# 0123-class-d-amp-max98365.net
KiCad netlist of a schematic drawn in EAGLE
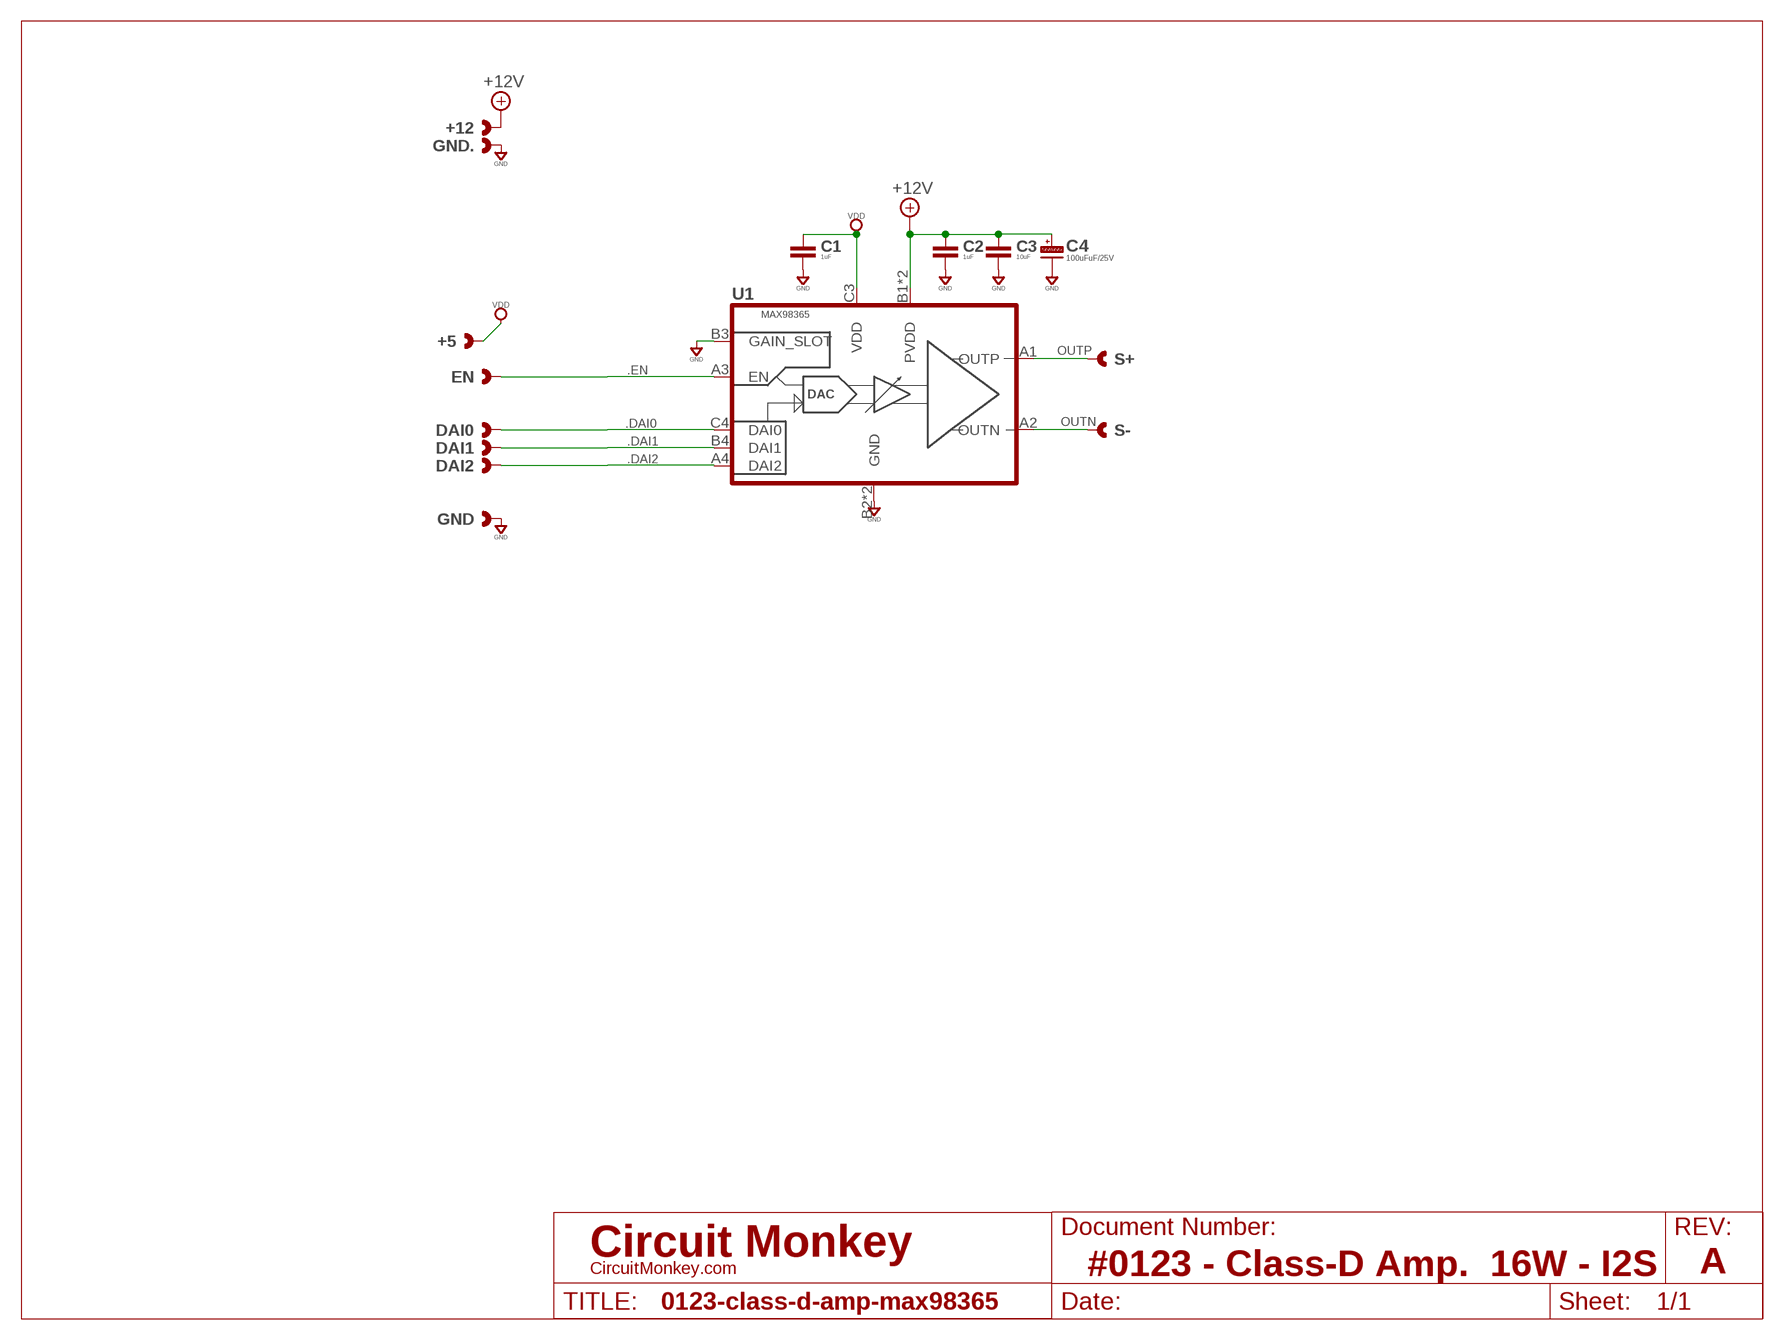
[diagram p0: schematic, sheet 1]

(export (version "E")
  (design (tool "Eeschema 10.0.6"))
  (components
    (comp (ref "+5")
      (value "CAST-01X12.00MM")
      (footprint "eagle-import:CAST01-2.00MM")
      (libsource (lib "eagle-import") (part "CAST-01X12.00MM"))
    )
    (comp (ref "+12")
      (value "CAST-01X12.00MM")
      (footprint "eagle-import:CAST01-2.00MM")
      (libsource (lib "eagle-import") (part "CAST-01X12.00MM"))
    )
    (comp (ref "C1")
      (value "1uF")
      (footprint "eagle-import:0603-CAP")
      (libsource (lib "eagle-import") (part "CAPACITOR0603"))
    )
    (comp (ref "C2")
      (value "1uF")
      (footprint "eagle-import:0603-CAP")
      (libsource (lib "eagle-import") (part "CAPACITOR0603"))
    )
    (comp (ref "C3")
      (value "10uF")
      (footprint "eagle-import:0603-CAP")
      (libsource (lib "eagle-import") (part "CAPACITOR0603"))
    )
    (comp (ref "C4")
      (value "100uFuF/25V")
      (footprint "eagle-import:CAP_ALUM_SMT_6.3")
      (libsource (lib "eagle-import") (part "CAPACITOR_POL-ALUM-SMT-6.3"))
    )
    (comp (ref "DAI0")
      (value "CAST-01X12.00MM")
      (footprint "eagle-import:CAST01-2.00MM")
      (libsource (lib "eagle-import") (part "CAST-01X12.00MM"))
    )
    (comp (ref "DAI1")
      (value "CAST-01X12.00MM")
      (footprint "eagle-import:CAST01-2.00MM")
      (libsource (lib "eagle-import") (part "CAST-01X12.00MM"))
    )
    (comp (ref "DAI2")
      (value "CAST-01X12.00MM")
      (footprint "eagle-import:CAST01-2.00MM")
      (libsource (lib "eagle-import") (part "CAST-01X12.00MM"))
    )
    (comp (ref "EN")
      (value "CAST-01X12.00MM")
      (footprint "eagle-import:CAST01-2.00MM")
      (libsource (lib "eagle-import") (part "CAST-01X12.00MM"))
    )
    (comp (ref "GND")
      (value "CAST-01X12.00MM")
      (footprint "eagle-import:CAST01-2.00MM")
      (libsource (lib "eagle-import") (part "CAST-01X12.00MM"))
    )
    (comp (ref "GND.")
      (value "CAST-01X12.00MM")
      (footprint "eagle-import:CAST01-2.00MM")
      (libsource (lib "eagle-import") (part "CAST-01X12.00MM"))
    )
    (comp (ref "S+")
      (value "CAST-01X12.00MM")
      (footprint "eagle-import:CAST01-2.00MM")
      (libsource (lib "eagle-import") (part "CAST-01X12.00MM"))
    )
    (comp (ref "S-")
      (value "CAST-01X12.00MM")
      (footprint "eagle-import:CAST01-2.00MM")
      (libsource (lib "eagle-import") (part "CAST-01X12.00MM"))
    )
    (comp (ref "U1")
      (value "MAX98365")
      (footprint "eagle-import:12WLP")
      (fields (field (name "MFR") "Maxim") (field (name "MPN") "MAX98365A/C"))
      (libsource (lib "eagle-import") (part "MAX98365"))
    )
  )
  (nets
    (net (code "1") (name "+12V") (class "Default")
      (node (ref "+12") (pin "1") (pinfunction "1_1") (pintype "bidirectional"))
      (node (ref "+12") (pin "P$1") (pinfunction "1_P$1") (pintype "bidirectional"))
      (node (ref "+12") (pin "P$2") (pinfunction "1_P$2") (pintype "bidirectional"))
      (node (ref "C2") (pin "1") (pinfunction "1_1") (pintype "passive"))
      (node (ref "C3") (pin "1") (pinfunction "1_1") (pintype "passive"))
      (node (ref "C4") (pin "+") (pinfunction "P_+") (pintype "bidirectional"))
      (node (ref "U1") (pin "B1") (pinfunction "PVDD_B1") (pintype "bidirectional"))
      (node (ref "U1") (pin "C1") (pinfunction "PVDD_C1") (pintype "bidirectional"))
    )
    (net (code "2") (name "/.DAI0") (class "Default")
      (node (ref "DAI0") (pin "1") (pinfunction "1_1") (pintype "bidirectional"))
      (node (ref "DAI0") (pin "P$1") (pinfunction "1_P$1") (pintype "bidirectional"))
      (node (ref "DAI0") (pin "P$2") (pinfunction "1_P$2") (pintype "bidirectional"))
      (node (ref "U1") (pin "C4") (pinfunction "DAI0_C4") (pintype "bidirectional"))
    )
    (net (code "3") (name "/.DAI1") (class "Default")
      (node (ref "DAI1") (pin "1") (pinfunction "1_1") (pintype "bidirectional"))
      (node (ref "DAI1") (pin "P$1") (pinfunction "1_P$1") (pintype "bidirectional"))
      (node (ref "DAI1") (pin "P$2") (pinfunction "1_P$2") (pintype "bidirectional"))
      (node (ref "U1") (pin "B4") (pinfunction "DAI1_B4") (pintype "bidirectional"))
    )
    (net (code "4") (name "/.DAI2") (class "Default")
      (node (ref "DAI2") (pin "1") (pinfunction "1_1") (pintype "bidirectional"))
      (node (ref "DAI2") (pin "P$1") (pinfunction "1_P$1") (pintype "bidirectional"))
      (node (ref "DAI2") (pin "P$2") (pinfunction "1_P$2") (pintype "bidirectional"))
      (node (ref "U1") (pin "A4") (pinfunction "DAI2_A4") (pintype "bidirectional"))
    )
    (net (code "5") (name "/.EN") (class "Default")
      (node (ref "EN") (pin "1") (pinfunction "1_1") (pintype "bidirectional"))
      (node (ref "EN") (pin "P$1") (pinfunction "1_P$1") (pintype "bidirectional"))
      (node (ref "EN") (pin "P$2") (pinfunction "1_P$2") (pintype "bidirectional"))
      (node (ref "U1") (pin "A3") (pinfunction "EN_A3") (pintype "bidirectional"))
    )
    (net (code "6") (name "/OUTN") (class "Default")
      (node (ref "S-") (pin "1") (pinfunction "1_1") (pintype "bidirectional"))
      (node (ref "S-") (pin "P$1") (pinfunction "1_P$1") (pintype "bidirectional"))
      (node (ref "S-") (pin "P$2") (pinfunction "1_P$2") (pintype "bidirectional"))
      (node (ref "U1") (pin "A2") (pinfunction "OUTN_A2") (pintype "bidirectional"))
    )
    (net (code "7") (name "/OUTP") (class "Default")
      (node (ref "S+") (pin "1") (pinfunction "1_1") (pintype "bidirectional"))
      (node (ref "S+") (pin "P$1") (pinfunction "1_P$1") (pintype "bidirectional"))
      (node (ref "S+") (pin "P$2") (pinfunction "1_P$2") (pintype "bidirectional"))
      (node (ref "U1") (pin "A1") (pinfunction "OUTP_A1") (pintype "bidirectional"))
    )
    (net (code "8") (name "GND") (class "Default")
      (node (ref "C1") (pin "2") (pinfunction "2_2") (pintype "passive"))
      (node (ref "C2") (pin "2") (pinfunction "2_2") (pintype "passive"))
      (node (ref "C3") (pin "2") (pinfunction "2_2") (pintype "passive"))
      (node (ref "C4") (pin "-") (pinfunction "N_-") (pintype "bidirectional"))
      (node (ref "GND") (pin "1") (pinfunction "1_1") (pintype "bidirectional"))
      (node (ref "GND") (pin "P$1") (pinfunction "1_P$1") (pintype "bidirectional"))
      (node (ref "GND") (pin "P$2") (pinfunction "1_P$2") (pintype "bidirectional"))
      (node (ref "GND.") (pin "1") (pinfunction "1_1") (pintype "bidirectional"))
      (node (ref "GND.") (pin "P$1") (pinfunction "1_P$1") (pintype "bidirectional"))
      (node (ref "GND.") (pin "P$2") (pinfunction "1_P$2") (pintype "bidirectional"))
      (node (ref "U1") (pin "B2") (pinfunction "GND_B2") (pintype "bidirectional"))
      (node (ref "U1") (pin "B3") (pinfunction "GAIN_SLOT_B3") (pintype "bidirectional"))
      (node (ref "U1") (pin "C2") (pinfunction "GND_C2") (pintype "bidirectional"))
    )
    (net (code "9") (name "VDD") (class "Default")
      (node (ref "+5") (pin "1") (pinfunction "1_1") (pintype "bidirectional"))
      (node (ref "+5") (pin "P$1") (pinfunction "1_P$1") (pintype "bidirectional"))
      (node (ref "+5") (pin "P$2") (pinfunction "1_P$2") (pintype "bidirectional"))
      (node (ref "C1") (pin "1") (pinfunction "1_1") (pintype "passive"))
      (node (ref "U1") (pin "C3") (pinfunction "VDD_C3") (pintype "bidirectional"))
    )
  )
)
